# Inverter16Smd.net
KiCad netlist of a schematic drawn in EAGLE
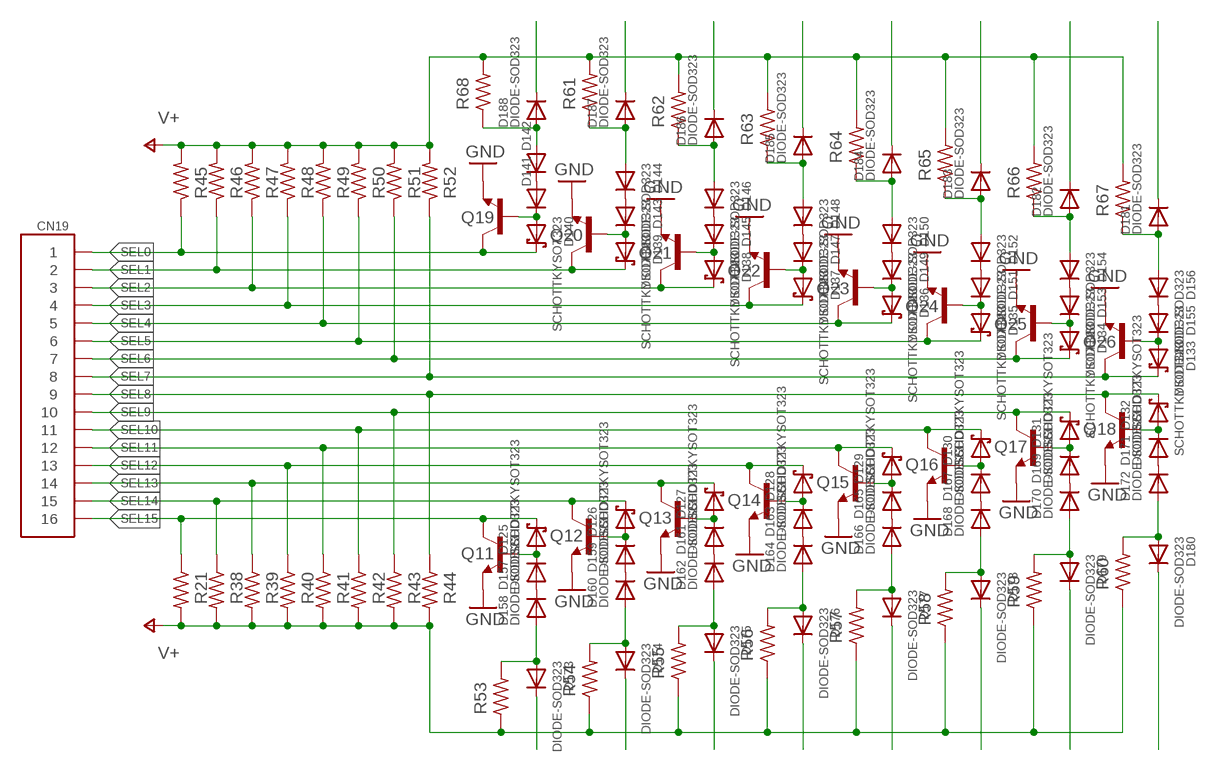
[diagram p0: schematic, sheet 1]

(export (version "E")
  (design (tool "Eeschema 10.0.6"))
  (components
    (comp (ref "CN19")
      (value "HD16")
      (footprint "eagle-import:HD16")
      (libsource (lib "eagle-import") (part "HD16"))
    )
    (comp (ref "D125")
      (value "SCHOTTKYSOT323")
      (footprint "eagle-import:SOT23")
      (libsource (lib "eagle-import") (part "SCHOTTKYSOT323"))
    )
    (comp (ref "D126")
      (value "SCHOTTKYSOT323")
      (footprint "eagle-import:SOT23")
      (libsource (lib "eagle-import") (part "SCHOTTKYSOT323"))
    )
    (comp (ref "D127")
      (value "SCHOTTKYSOT323")
      (footprint "eagle-import:SOT23")
      (libsource (lib "eagle-import") (part "SCHOTTKYSOT323"))
    )
    (comp (ref "D128")
      (value "SCHOTTKYSOT323")
      (footprint "eagle-import:SOT23")
      (libsource (lib "eagle-import") (part "SCHOTTKYSOT323"))
    )
    (comp (ref "D129")
      (value "SCHOTTKYSOT323")
      (footprint "eagle-import:SOT23")
      (libsource (lib "eagle-import") (part "SCHOTTKYSOT323"))
    )
    (comp (ref "D130")
      (value "SCHOTTKYSOT323")
      (footprint "eagle-import:SOT23")
      (libsource (lib "eagle-import") (part "SCHOTTKYSOT323"))
    )
    (comp (ref "D131")
      (value "SCHOTTKYSOT323")
      (footprint "eagle-import:SOT23")
      (libsource (lib "eagle-import") (part "SCHOTTKYSOT323"))
    )
    (comp (ref "D132")
      (value "SCHOTTKYSOT323")
      (footprint "eagle-import:SOT23")
      (libsource (lib "eagle-import") (part "SCHOTTKYSOT323"))
    )
    (comp (ref "D133")
      (value "SCHOTTKYSOT323")
      (footprint "eagle-import:SOT23")
      (libsource (lib "eagle-import") (part "SCHOTTKYSOT323"))
    )
    (comp (ref "D134")
      (value "SCHOTTKYSOT323")
      (footprint "eagle-import:SOT23")
      (libsource (lib "eagle-import") (part "SCHOTTKYSOT323"))
    )
    (comp (ref "D135")
      (value "SCHOTTKYSOT323")
      (footprint "eagle-import:SOT23")
      (libsource (lib "eagle-import") (part "SCHOTTKYSOT323"))
    )
    (comp (ref "D136")
      (value "SCHOTTKYSOT323")
      (footprint "eagle-import:SOT23")
      (libsource (lib "eagle-import") (part "SCHOTTKYSOT323"))
    )
    (comp (ref "D137")
      (value "SCHOTTKYSOT323")
      (footprint "eagle-import:SOT23")
      (libsource (lib "eagle-import") (part "SCHOTTKYSOT323"))
    )
    (comp (ref "D138")
      (value "SCHOTTKYSOT323")
      (footprint "eagle-import:SOT23")
      (libsource (lib "eagle-import") (part "SCHOTTKYSOT323"))
    )
    (comp (ref "D139")
      (value "SCHOTTKYSOT323")
      (footprint "eagle-import:SOT23")
      (libsource (lib "eagle-import") (part "SCHOTTKYSOT323"))
    )
    (comp (ref "D140")
      (value "SCHOTTKYSOT323")
      (footprint "eagle-import:SOT23")
      (libsource (lib "eagle-import") (part "SCHOTTKYSOT323"))
    )
    (comp (ref "D141")
      (value "DIODE-SOD323")
      (footprint "eagle-import:SOD323F")
      (libsource (lib "eagle-import") (part "DIODE-SOD323"))
    )
    (comp (ref "D142")
      (value "DIODE-SOD323")
      (footprint "eagle-import:SOD323F")
      (libsource (lib "eagle-import") (part "DIODE-SOD323"))
    )
    (comp (ref "D143")
      (value "DIODE-SOD323")
      (footprint "eagle-import:SOD323F")
      (libsource (lib "eagle-import") (part "DIODE-SOD323"))
    )
    (comp (ref "D144")
      (value "DIODE-SOD323")
      (footprint "eagle-import:SOD323F")
      (libsource (lib "eagle-import") (part "DIODE-SOD323"))
    )
    (comp (ref "D145")
      (value "DIODE-SOD323")
      (footprint "eagle-import:SOD323F")
      (libsource (lib "eagle-import") (part "DIODE-SOD323"))
    )
    (comp (ref "D146")
      (value "DIODE-SOD323")
      (footprint "eagle-import:SOD323F")
      (libsource (lib "eagle-import") (part "DIODE-SOD323"))
    )
    (comp (ref "D147")
      (value "DIODE-SOD323")
      (footprint "eagle-import:SOD323F")
      (libsource (lib "eagle-import") (part "DIODE-SOD323"))
    )
    (comp (ref "D148")
      (value "DIODE-SOD323")
      (footprint "eagle-import:SOD323F")
      (libsource (lib "eagle-import") (part "DIODE-SOD323"))
    )
    (comp (ref "D149")
      (value "DIODE-SOD323")
      (footprint "eagle-import:SOD323F")
      (libsource (lib "eagle-import") (part "DIODE-SOD323"))
    )
    (comp (ref "D150")
      (value "DIODE-SOD323")
      (footprint "eagle-import:SOD323F")
      (libsource (lib "eagle-import") (part "DIODE-SOD323"))
    )
    (comp (ref "D151")
      (value "DIODE-SOD323")
      (footprint "eagle-import:SOD323F")
      (libsource (lib "eagle-import") (part "DIODE-SOD323"))
    )
    (comp (ref "D152")
      (value "DIODE-SOD323")
      (footprint "eagle-import:SOD323F")
      (libsource (lib "eagle-import") (part "DIODE-SOD323"))
    )
    (comp (ref "D153")
      (value "DIODE-SOD323")
      (footprint "eagle-import:SOD323F")
      (libsource (lib "eagle-import") (part "DIODE-SOD323"))
    )
    (comp (ref "D154")
      (value "DIODE-SOD323")
      (footprint "eagle-import:SOD323F")
      (libsource (lib "eagle-import") (part "DIODE-SOD323"))
    )
    (comp (ref "D155")
      (value "DIODE-SOD323")
      (footprint "eagle-import:SOD323F")
      (libsource (lib "eagle-import") (part "DIODE-SOD323"))
    )
    (comp (ref "D156")
      (value "DIODE-SOD323")
      (footprint "eagle-import:SOD323F")
      (libsource (lib "eagle-import") (part "DIODE-SOD323"))
    )
    (comp (ref "D157")
      (value "DIODE-SOD323")
      (footprint "eagle-import:SOD323F")
      (libsource (lib "eagle-import") (part "DIODE-SOD323"))
    )
    (comp (ref "D158")
      (value "DIODE-SOD323")
      (footprint "eagle-import:SOD323F")
      (libsource (lib "eagle-import") (part "DIODE-SOD323"))
    )
    (comp (ref "D159")
      (value "DIODE-SOD323")
      (footprint "eagle-import:SOD323F")
      (libsource (lib "eagle-import") (part "DIODE-SOD323"))
    )
    (comp (ref "D160")
      (value "DIODE-SOD323")
      (footprint "eagle-import:SOD323F")
      (libsource (lib "eagle-import") (part "DIODE-SOD323"))
    )
    (comp (ref "D161")
      (value "DIODE-SOD323")
      (footprint "eagle-import:SOD323F")
      (libsource (lib "eagle-import") (part "DIODE-SOD323"))
    )
    (comp (ref "D162")
      (value "DIODE-SOD323")
      (footprint "eagle-import:SOD323F")
      (libsource (lib "eagle-import") (part "DIODE-SOD323"))
    )
    (comp (ref "D163")
      (value "DIODE-SOD323")
      (footprint "eagle-import:SOD323F")
      (libsource (lib "eagle-import") (part "DIODE-SOD323"))
    )
    (comp (ref "D164")
      (value "DIODE-SOD323")
      (footprint "eagle-import:SOD323F")
      (libsource (lib "eagle-import") (part "DIODE-SOD323"))
    )
    (comp (ref "D165")
      (value "DIODE-SOD323")
      (footprint "eagle-import:SOD323F")
      (libsource (lib "eagle-import") (part "DIODE-SOD323"))
    )
    (comp (ref "D166")
      (value "DIODE-SOD323")
      (footprint "eagle-import:SOD323F")
      (libsource (lib "eagle-import") (part "DIODE-SOD323"))
    )
    (comp (ref "D167")
      (value "DIODE-SOD323")
      (footprint "eagle-import:SOD323F")
      (libsource (lib "eagle-import") (part "DIODE-SOD323"))
    )
    (comp (ref "D168")
      (value "DIODE-SOD323")
      (footprint "eagle-import:SOD323F")
      (libsource (lib "eagle-import") (part "DIODE-SOD323"))
    )
    (comp (ref "D169")
      (value "DIODE-SOD323")
      (footprint "eagle-import:SOD323F")
      (libsource (lib "eagle-import") (part "DIODE-SOD323"))
    )
    (comp (ref "D170")
      (value "DIODE-SOD323")
      (footprint "eagle-import:SOD323F")
      (libsource (lib "eagle-import") (part "DIODE-SOD323"))
    )
    (comp (ref "D171")
      (value "DIODE-SOD323")
      (footprint "eagle-import:SOD323F")
      (libsource (lib "eagle-import") (part "DIODE-SOD323"))
    )
    (comp (ref "D172")
      (value "DIODE-SOD323")
      (footprint "eagle-import:SOD323F")
      (libsource (lib "eagle-import") (part "DIODE-SOD323"))
    )
    (comp (ref "D173")
      (value "DIODE-SOD323")
      (footprint "eagle-import:SOD323F")
      (libsource (lib "eagle-import") (part "DIODE-SOD323"))
    )
    (comp (ref "D174")
      (value "DIODE-SOD323")
      (footprint "eagle-import:SOD323F")
      (libsource (lib "eagle-import") (part "DIODE-SOD323"))
    )
    (comp (ref "D175")
      (value "DIODE-SOD323")
      (footprint "eagle-import:SOD323F")
      (libsource (lib "eagle-import") (part "DIODE-SOD323"))
    )
    (comp (ref "D176")
      (value "DIODE-SOD323")
      (footprint "eagle-import:SOD323F")
      (libsource (lib "eagle-import") (part "DIODE-SOD323"))
    )
    (comp (ref "D177")
      (value "DIODE-SOD323")
      (footprint "eagle-import:SOD323F")
      (libsource (lib "eagle-import") (part "DIODE-SOD323"))
    )
    (comp (ref "D178")
      (value "DIODE-SOD323")
      (footprint "eagle-import:SOD323F")
      (libsource (lib "eagle-import") (part "DIODE-SOD323"))
    )
    (comp (ref "D179")
      (value "DIODE-SOD323")
      (footprint "eagle-import:SOD323F")
      (libsource (lib "eagle-import") (part "DIODE-SOD323"))
    )
    (comp (ref "D180")
      (value "DIODE-SOD323")
      (footprint "eagle-import:SOD323F")
      (libsource (lib "eagle-import") (part "DIODE-SOD323"))
    )
    (comp (ref "D181")
      (value "DIODE-SOD323")
      (footprint "eagle-import:SOD323F")
      (libsource (lib "eagle-import") (part "DIODE-SOD323"))
    )
    (comp (ref "D182")
      (value "DIODE-SOD323")
      (footprint "eagle-import:SOD323F")
      (libsource (lib "eagle-import") (part "DIODE-SOD323"))
    )
    (comp (ref "D183")
      (value "DIODE-SOD323")
      (footprint "eagle-import:SOD323F")
      (libsource (lib "eagle-import") (part "DIODE-SOD323"))
    )
    (comp (ref "D184")
      (value "DIODE-SOD323")
      (footprint "eagle-import:SOD323F")
      (libsource (lib "eagle-import") (part "DIODE-SOD323"))
    )
    (comp (ref "D185")
      (value "DIODE-SOD323")
      (footprint "eagle-import:SOD323F")
      (libsource (lib "eagle-import") (part "DIODE-SOD323"))
    )
    (comp (ref "D186")
      (value "DIODE-SOD323")
      (footprint "eagle-import:SOD323F")
      (libsource (lib "eagle-import") (part "DIODE-SOD323"))
    )
    (comp (ref "D187")
      (value "DIODE-SOD323")
      (footprint "eagle-import:SOD323F")
      (libsource (lib "eagle-import") (part "DIODE-SOD323"))
    )
    (comp (ref "D188")
      (value "DIODE-SOD323")
      (footprint "eagle-import:SOD323F")
      (libsource (lib "eagle-import") (part "DIODE-SOD323"))
    )
    (comp (ref "Q11")
      (value "BC547-SOT23")
      (footprint "eagle-import:SOT23")
      (libsource (lib "eagle-import") (part "BC547-SOT23"))
    )
    (comp (ref "Q12")
      (value "BC547-SOT23")
      (footprint "eagle-import:SOT23")
      (libsource (lib "eagle-import") (part "BC547-SOT23"))
    )
    (comp (ref "Q13")
      (value "BC547-SOT23")
      (footprint "eagle-import:SOT23")
      (libsource (lib "eagle-import") (part "BC547-SOT23"))
    )
    (comp (ref "Q14")
      (value "BC547-SOT23")
      (footprint "eagle-import:SOT23")
      (libsource (lib "eagle-import") (part "BC547-SOT23"))
    )
    (comp (ref "Q15")
      (value "BC547-SOT23")
      (footprint "eagle-import:SOT23")
      (libsource (lib "eagle-import") (part "BC547-SOT23"))
    )
    (comp (ref "Q16")
      (value "BC547-SOT23")
      (footprint "eagle-import:SOT23")
      (libsource (lib "eagle-import") (part "BC547-SOT23"))
    )
    (comp (ref "Q17")
      (value "BC547-SOT23")
      (footprint "eagle-import:SOT23")
      (libsource (lib "eagle-import") (part "BC547-SOT23"))
    )
    (comp (ref "Q18")
      (value "BC547-SOT23")
      (footprint "eagle-import:SOT23")
      (libsource (lib "eagle-import") (part "BC547-SOT23"))
    )
    (comp (ref "Q19")
      (value "BC547-SOT23")
      (footprint "eagle-import:SOT23")
      (libsource (lib "eagle-import") (part "BC547-SOT23"))
    )
    (comp (ref "Q20")
      (value "BC547-SOT23")
      (footprint "eagle-import:SOT23")
      (libsource (lib "eagle-import") (part "BC547-SOT23"))
    )
    (comp (ref "Q21")
      (value "BC547-SOT23")
      (footprint "eagle-import:SOT23")
      (libsource (lib "eagle-import") (part "BC547-SOT23"))
    )
    (comp (ref "Q22")
      (value "BC547-SOT23")
      (footprint "eagle-import:SOT23")
      (libsource (lib "eagle-import") (part "BC547-SOT23"))
    )
    (comp (ref "Q23")
      (value "BC547-SOT23")
      (footprint "eagle-import:SOT23")
      (libsource (lib "eagle-import") (part "BC547-SOT23"))
    )
    (comp (ref "Q24")
      (value "BC547-SOT23")
      (footprint "eagle-import:SOT23")
      (libsource (lib "eagle-import") (part "BC547-SOT23"))
    )
    (comp (ref "Q25")
      (value "BC547-SOT23")
      (footprint "eagle-import:SOT23")
      (libsource (lib "eagle-import") (part "BC547-SOT23"))
    )
    (comp (ref "Q26")
      (value "BC547-SOT23")
      (footprint "eagle-import:SOT23")
      (libsource (lib "eagle-import") (part "BC547-SOT23"))
    )
    (comp (ref "R21")
      (value "R-0805")
      (footprint "eagle-import:R0805")
      (libsource (lib "eagle-import") (part "R-0805"))
    )
    (comp (ref "R38")
      (value "R-0805")
      (footprint "eagle-import:R0805")
      (libsource (lib "eagle-import") (part "R-0805"))
    )
    (comp (ref "R39")
      (value "R-0805")
      (footprint "eagle-import:R0805")
      (libsource (lib "eagle-import") (part "R-0805"))
    )
    (comp (ref "R40")
      (value "R-0805")
      (footprint "eagle-import:R0805")
      (libsource (lib "eagle-import") (part "R-0805"))
    )
    (comp (ref "R41")
      (value "R-0805")
      (footprint "eagle-import:R0805")
      (libsource (lib "eagle-import") (part "R-0805"))
    )
    (comp (ref "R42")
      (value "R-0805")
      (footprint "eagle-import:R0805")
      (libsource (lib "eagle-import") (part "R-0805"))
    )
    (comp (ref "R43")
      (value "R-0805")
      (footprint "eagle-import:R0805")
      (libsource (lib "eagle-import") (part "R-0805"))
    )
    (comp (ref "R44")
      (value "R-0805")
      (footprint "eagle-import:R0805")
      (libsource (lib "eagle-import") (part "R-0805"))
    )
    (comp (ref "R45")
      (value "R-0805")
      (footprint "eagle-import:R0805")
      (libsource (lib "eagle-import") (part "R-0805"))
    )
    (comp (ref "R46")
      (value "R-0805")
      (footprint "eagle-import:R0805")
      (libsource (lib "eagle-import") (part "R-0805"))
    )
    (comp (ref "R47")
      (value "R-0805")
      (footprint "eagle-import:R0805")
      (libsource (lib "eagle-import") (part "R-0805"))
    )
    (comp (ref "R48")
      (value "R-0805")
      (footprint "eagle-import:R0805")
      (libsource (lib "eagle-import") (part "R-0805"))
    )
    (comp (ref "R49")
      (value "R-0805")
      (footprint "eagle-import:R0805")
      (libsource (lib "eagle-import") (part "R-0805"))
    )
    (comp (ref "R50")
      (value "R-0805")
      (footprint "eagle-import:R0805")
      (libsource (lib "eagle-import") (part "R-0805"))
    )
    (comp (ref "R51")
      (value "R-0805")
      (footprint "eagle-import:R0805")
      (libsource (lib "eagle-import") (part "R-0805"))
    )
    (comp (ref "R52")
      (value "R-0805")
      (footprint "eagle-import:R0805")
      (libsource (lib "eagle-import") (part "R-0805"))
    )
    (comp (ref "R53")
      (value "R-0805")
      (footprint "eagle-import:R0805")
      (libsource (lib "eagle-import") (part "R-0805"))
    )
    (comp (ref "R54")
      (value "R-0805")
      (footprint "eagle-import:R0805")
      (libsource (lib "eagle-import") (part "R-0805"))
    )
    (comp (ref "R55")
      (value "R-0805")
      (footprint "eagle-import:R0805")
      (libsource (lib "eagle-import") (part "R-0805"))
    )
    (comp (ref "R56")
      (value "R-0805")
      (footprint "eagle-import:R0805")
      (libsource (lib "eagle-import") (part "R-0805"))
    )
    (comp (ref "R57")
      (value "R-0805")
      (footprint "eagle-import:R0805")
      (libsource (lib "eagle-import") (part "R-0805"))
    )
    (comp (ref "R58")
      (value "R-0805")
      (footprint "eagle-import:R0805")
      (libsource (lib "eagle-import") (part "R-0805"))
    )
    (comp (ref "R59")
      (value "R-0805")
      (footprint "eagle-import:R0805")
      (libsource (lib "eagle-import") (part "R-0805"))
    )
    (comp (ref "R60")
      (value "R-0805")
      (footprint "eagle-import:R0805")
      (libsource (lib "eagle-import") (part "R-0805"))
    )
    (comp (ref "R61")
      (value "R-0805")
      (footprint "eagle-import:R0805")
      (libsource (lib "eagle-import") (part "R-0805"))
    )
    (comp (ref "R62")
      (value "R-0805")
      (footprint "eagle-import:R0805")
      (libsource (lib "eagle-import") (part "R-0805"))
    )
    (comp (ref "R63")
      (value "R-0805")
      (footprint "eagle-import:R0805")
      (libsource (lib "eagle-import") (part "R-0805"))
    )
    (comp (ref "R64")
      (value "R-0805")
      (footprint "eagle-import:R0805")
      (libsource (lib "eagle-import") (part "R-0805"))
    )
    (comp (ref "R65")
      (value "R-0805")
      (footprint "eagle-import:R0805")
      (libsource (lib "eagle-import") (part "R-0805"))
    )
    (comp (ref "R66")
      (value "R-0805")
      (footprint "eagle-import:R0805")
      (libsource (lib "eagle-import") (part "R-0805"))
    )
    (comp (ref "R67")
      (value "R-0805")
      (footprint "eagle-import:R0805")
      (libsource (lib "eagle-import") (part "R-0805"))
    )
    (comp (ref "R68")
      (value "R-0805")
      (footprint "eagle-import:R0805")
      (libsource (lib "eagle-import") (part "R-0805"))
    )
  )
  (nets
    (net (code "1") (name "GND") (class "Default")
      (node (ref "Q11") (pin "2") (pinfunction "E_2") (pintype "passive"))
      (node (ref "Q12") (pin "2") (pinfunction "E_2") (pintype "passive"))
      (node (ref "Q13") (pin "2") (pinfunction "E_2") (pintype "passive"))
      (node (ref "Q14") (pin "2") (pinfunction "E_2") (pintype "passive"))
      (node (ref "Q15") (pin "2") (pinfunction "E_2") (pintype "passive"))
      (node (ref "Q16") (pin "2") (pinfunction "E_2") (pintype "passive"))
      (node (ref "Q17") (pin "2") (pinfunction "E_2") (pintype "passive"))
      (node (ref "Q18") (pin "2") (pinfunction "E_2") (pintype "passive"))
      (node (ref "Q19") (pin "2") (pinfunction "E_2") (pintype "passive"))
      (node (ref "Q20") (pin "2") (pinfunction "E_2") (pintype "passive"))
      (node (ref "Q21") (pin "2") (pinfunction "E_2") (pintype "passive"))
      (node (ref "Q22") (pin "2") (pinfunction "E_2") (pintype "passive"))
      (node (ref "Q23") (pin "2") (pinfunction "E_2") (pintype "passive"))
      (node (ref "Q24") (pin "2") (pinfunction "E_2") (pintype "passive"))
      (node (ref "Q25") (pin "2") (pinfunction "E_2") (pintype "passive"))
      (node (ref "Q26") (pin "2") (pinfunction "E_2") (pintype "passive"))
    )
    (net (code "2") (name "Net-(D125-A)") (class "Default")
      (node (ref "D125") (pin "1") (pinfunction "A_1") (pintype "passive"))
      (node (ref "D157") (pin "C") (pinfunction "C_C") (pintype "passive"))
      (node (ref "Q11") (pin "1") (pinfunction "B_1") (pintype "passive"))
    )
    (net (code "3") (name "Net-(D126-A)") (class "Default")
      (node (ref "D126") (pin "1") (pinfunction "A_1") (pintype "passive"))
      (node (ref "D159") (pin "C") (pinfunction "C_C") (pintype "passive"))
      (node (ref "Q12") (pin "1") (pinfunction "B_1") (pintype "passive"))
    )
    (net (code "4") (name "Net-(D127-A)") (class "Default")
      (node (ref "D127") (pin "1") (pinfunction "A_1") (pintype "passive"))
      (node (ref "D161") (pin "C") (pinfunction "C_C") (pintype "passive"))
      (node (ref "Q13") (pin "1") (pinfunction "B_1") (pintype "passive"))
    )
    (net (code "5") (name "Net-(D128-A)") (class "Default")
      (node (ref "D128") (pin "1") (pinfunction "A_1") (pintype "passive"))
      (node (ref "D163") (pin "C") (pinfunction "C_C") (pintype "passive"))
      (node (ref "Q14") (pin "1") (pinfunction "B_1") (pintype "passive"))
    )
    (net (code "6") (name "Net-(D129-A)") (class "Default")
      (node (ref "D129") (pin "1") (pinfunction "A_1") (pintype "passive"))
      (node (ref "D165") (pin "C") (pinfunction "C_C") (pintype "passive"))
      (node (ref "Q15") (pin "1") (pinfunction "B_1") (pintype "passive"))
    )
    (net (code "7") (name "Net-(D130-A)") (class "Default")
      (node (ref "D130") (pin "1") (pinfunction "A_1") (pintype "passive"))
      (node (ref "D167") (pin "C") (pinfunction "C_C") (pintype "passive"))
      (node (ref "Q16") (pin "1") (pinfunction "B_1") (pintype "passive"))
    )
    (net (code "8") (name "Net-(D131-A)") (class "Default")
      (node (ref "D131") (pin "1") (pinfunction "A_1") (pintype "passive"))
      (node (ref "D169") (pin "C") (pinfunction "C_C") (pintype "passive"))
      (node (ref "Q17") (pin "1") (pinfunction "B_1") (pintype "passive"))
    )
    (net (code "9") (name "Net-(D132-A)") (class "Default")
      (node (ref "D132") (pin "1") (pinfunction "A_1") (pintype "passive"))
      (node (ref "D171") (pin "C") (pinfunction "C_C") (pintype "passive"))
      (node (ref "Q18") (pin "1") (pinfunction "B_1") (pintype "passive"))
    )
    (net (code "10") (name "Net-(D133-A)") (class "Default")
      (node (ref "D133") (pin "1") (pinfunction "A_1") (pintype "passive"))
      (node (ref "D155") (pin "C") (pinfunction "C_C") (pintype "passive"))
      (node (ref "Q26") (pin "1") (pinfunction "B_1") (pintype "passive"))
    )
    (net (code "11") (name "Net-(D134-A)") (class "Default")
      (node (ref "D134") (pin "1") (pinfunction "A_1") (pintype "passive"))
      (node (ref "D153") (pin "C") (pinfunction "C_C") (pintype "passive"))
      (node (ref "Q25") (pin "1") (pinfunction "B_1") (pintype "passive"))
    )
    (net (code "12") (name "Net-(D135-A)") (class "Default")
      (node (ref "D135") (pin "1") (pinfunction "A_1") (pintype "passive"))
      (node (ref "D151") (pin "C") (pinfunction "C_C") (pintype "passive"))
      (node (ref "Q24") (pin "1") (pinfunction "B_1") (pintype "passive"))
    )
    (net (code "13") (name "Net-(D136-A)") (class "Default")
      (node (ref "D136") (pin "1") (pinfunction "A_1") (pintype "passive"))
      (node (ref "D149") (pin "C") (pinfunction "C_C") (pintype "passive"))
      (node (ref "Q23") (pin "1") (pinfunction "B_1") (pintype "passive"))
    )
    (net (code "14") (name "Net-(D137-A)") (class "Default")
      (node (ref "D137") (pin "1") (pinfunction "A_1") (pintype "passive"))
      (node (ref "D147") (pin "C") (pinfunction "C_C") (pintype "passive"))
      (node (ref "Q22") (pin "1") (pinfunction "B_1") (pintype "passive"))
    )
    (net (code "15") (name "Net-(D138-A)") (class "Default")
      (node (ref "D138") (pin "1") (pinfunction "A_1") (pintype "passive"))
      (node (ref "D145") (pin "C") (pinfunction "C_C") (pintype "passive"))
      (node (ref "Q21") (pin "1") (pinfunction "B_1") (pintype "passive"))
    )
    (net (code "16") (name "Net-(D139-A)") (class "Default")
      (node (ref "D139") (pin "1") (pinfunction "A_1") (pintype "passive"))
      (node (ref "D143") (pin "C") (pinfunction "C_C") (pintype "passive"))
      (node (ref "Q20") (pin "1") (pinfunction "B_1") (pintype "passive"))
    )
    (net (code "17") (name "Net-(D140-A)") (class "Default")
      (node (ref "D140") (pin "1") (pinfunction "A_1") (pintype "passive"))
      (node (ref "D141") (pin "C") (pinfunction "C_C") (pintype "passive"))
      (node (ref "Q19") (pin "1") (pinfunction "B_1") (pintype "passive"))
    )
    (net (code "18") (name "Net-(D141-PadA)") (class "Default")
      (node (ref "D141") (pin "A") (pinfunction "A_A") (pintype "passive"))
      (node (ref "D142") (pin "C") (pinfunction "C_C") (pintype "passive"))
    )
    (net (code "19") (name "Net-(D142-PadA)") (class "Default")
      (node (ref "D142") (pin "A") (pinfunction "A_A") (pintype "passive"))
      (node (ref "D188") (pin "A") (pinfunction "A_A") (pintype "passive"))
      (node (ref "R68") (pin "1") (pinfunction "1_1") (pintype "passive"))
    )
    (net (code "20") (name "Net-(D143-PadA)") (class "Default")
      (node (ref "D143") (pin "A") (pinfunction "A_A") (pintype "passive"))
      (node (ref "D144") (pin "C") (pinfunction "C_C") (pintype "passive"))
    )
    (net (code "21") (name "Net-(D144-PadA)") (class "Default")
      (node (ref "D144") (pin "A") (pinfunction "A_A") (pintype "passive"))
      (node (ref "D187") (pin "A") (pinfunction "A_A") (pintype "passive"))
      (node (ref "R61") (pin "1") (pinfunction "1_1") (pintype "passive"))
    )
    (net (code "22") (name "Net-(D145-PadA)") (class "Default")
      (node (ref "D145") (pin "A") (pinfunction "A_A") (pintype "passive"))
      (node (ref "D146") (pin "C") (pinfunction "C_C") (pintype "passive"))
    )
    (net (code "23") (name "Net-(D146-PadA)") (class "Default")
      (node (ref "D146") (pin "A") (pinfunction "A_A") (pintype "passive"))
      (node (ref "D186") (pin "A") (pinfunction "A_A") (pintype "passive"))
      (node (ref "R62") (pin "1") (pinfunction "1_1") (pintype "passive"))
    )
    (net (code "24") (name "Net-(D147-PadA)") (class "Default")
      (node (ref "D147") (pin "A") (pinfunction "A_A") (pintype "passive"))
      (node (ref "D148") (pin "C") (pinfunction "C_C") (pintype "passive"))
    )
    (net (code "25") (name "Net-(D148-PadA)") (class "Default")
      (node (ref "D148") (pin "A") (pinfunction "A_A") (pintype "passive"))
      (node (ref "D185") (pin "A") (pinfunction "A_A") (pintype "passive"))
      (node (ref "R63") (pin "1") (pinfunction "1_1") (pintype "passive"))
    )
    (net (code "26") (name "Net-(D149-PadA)") (class "Default")
      (node (ref "D149") (pin "A") (pinfunction "A_A") (pintype "passive"))
      (node (ref "D150") (pin "C") (pinfunction "C_C") (pintype "passive"))
    )
    (net (code "27") (name "Net-(D150-PadA)") (class "Default")
      (node (ref "D150") (pin "A") (pinfunction "A_A") (pintype "passive"))
      (node (ref "D184") (pin "A") (pinfunction "A_A") (pintype "passive"))
      (node (ref "R64") (pin "1") (pinfunction "1_1") (pintype "passive"))
    )
    (net (code "28") (name "Net-(D151-PadA)") (class "Default")
      (node (ref "D151") (pin "A") (pinfunction "A_A") (pintype "passive"))
      (node (ref "D152") (pin "C") (pinfunction "C_C") (pintype "passive"))
    )
    (net (code "29") (name "Net-(D152-PadA)") (class "Default")
      (node (ref "D152") (pin "A") (pinfunction "A_A") (pintype "passive"))
      (node (ref "D183") (pin "A") (pinfunction "A_A") (pintype "passive"))
      (node (ref "R65") (pin "1") (pinfunction "1_1") (pintype "passive"))
    )
    (net (code "30") (name "Net-(D153-PadA)") (class "Default")
      (node (ref "D153") (pin "A") (pinfunction "A_A") (pintype "passive"))
      (node (ref "D154") (pin "C") (pinfunction "C_C") (pintype "passive"))
    )
    (net (code "31") (name "Net-(D154-PadA)") (class "Default")
      (node (ref "D154") (pin "A") (pinfunction "A_A") (pintype "passive"))
      (node (ref "D182") (pin "A") (pinfunction "A_A") (pintype "passive"))
      (node (ref "R66") (pin "1") (pinfunction "1_1") (pintype "passive"))
    )
    (net (code "32") (name "Net-(D155-PadA)") (class "Default")
      (node (ref "D155") (pin "A") (pinfunction "A_A") (pintype "passive"))
      (node (ref "D156") (pin "C") (pinfunction "C_C") (pintype "passive"))
    )
    (net (code "33") (name "Net-(D156-PadA)") (class "Default")
      (node (ref "D156") (pin "A") (pinfunction "A_A") (pintype "passive"))
      (node (ref "D181") (pin "A") (pinfunction "A_A") (pintype "passive"))
      (node (ref "R67") (pin "1") (pinfunction "1_1") (pintype "passive"))
    )
    (net (code "34") (name "Net-(D157-PadA)") (class "Default")
      (node (ref "D157") (pin "A") (pinfunction "A_A") (pintype "passive"))
      (node (ref "D158") (pin "C") (pinfunction "C_C") (pintype "passive"))
    )
    (net (code "35") (name "Net-(D158-PadA)") (class "Default")
      (node (ref "D158") (pin "A") (pinfunction "A_A") (pintype "passive"))
      (node (ref "D173") (pin "A") (pinfunction "A_A") (pintype "passive"))
      (node (ref "R53") (pin "2") (pinfunction "2_2") (pintype "passive"))
    )
    (net (code "36") (name "Net-(D159-PadA)") (class "Default")
      (node (ref "D159") (pin "A") (pinfunction "A_A") (pintype "passive"))
      (node (ref "D160") (pin "C") (pinfunction "C_C") (pintype "passive"))
    )
    (net (code "37") (name "Net-(D160-PadA)") (class "Default")
      (node (ref "D160") (pin "A") (pinfunction "A_A") (pintype "passive"))
      (node (ref "D174") (pin "A") (pinfunction "A_A") (pintype "passive"))
      (node (ref "R54") (pin "2") (pinfunction "2_2") (pintype "passive"))
    )
    (net (code "38") (name "Net-(D161-PadA)") (class "Default")
      (node (ref "D161") (pin "A") (pinfunction "A_A") (pintype "passive"))
      (node (ref "D162") (pin "C") (pinfunction "C_C") (pintype "passive"))
    )
    (net (code "39") (name "Net-(D162-PadA)") (class "Default")
      (node (ref "D162") (pin "A") (pinfunction "A_A") (pintype "passive"))
      (node (ref "D175") (pin "A") (pinfunction "A_A") (pintype "passive"))
      (node (ref "R55") (pin "2") (pinfunction "2_2") (pintype "passive"))
    )
    (net (code "40") (name "Net-(D163-PadA)") (class "Default")
      (node (ref "D163") (pin "A") (pinfunction "A_A") (pintype "passive"))
      (node (ref "D164") (pin "C") (pinfunction "C_C") (pintype "passive"))
    )
    (net (code "41") (name "Net-(D164-PadA)") (class "Default")
      (node (ref "D164") (pin "A") (pinfunction "A_A") (pintype "passive"))
      (node (ref "D176") (pin "A") (pinfunction "A_A") (pintype "passive"))
      (node (ref "R56") (pin "2") (pinfunction "2_2") (pintype "passive"))
    )
    (net (code "42") (name "Net-(D165-PadA)") (class "Default")
      (node (ref "D165") (pin "A") (pinfunction "A_A") (pintype "passive"))
      (node (ref "D166") (pin "C") (pinfunction "C_C") (pintype "passive"))
    )
    (net (code "43") (name "Net-(D166-PadA)") (class "Default")
      (node (ref "D166") (pin "A") (pinfunction "A_A") (pintype "passive"))
      (node (ref "D177") (pin "A") (pinfunction "A_A") (pintype "passive"))
      (node (ref "R57") (pin "2") (pinfunction "2_2") (pintype "passive"))
    )
    (net (code "44") (name "Net-(D167-PadA)") (class "Default")
      (node (ref "D167") (pin "A") (pinfunction "A_A") (pintype "passive"))
      (node (ref "D168") (pin "C") (pinfunction "C_C") (pintype "passive"))
    )
    (net (code "45") (name "Net-(D168-PadA)") (class "Default")
      (node (ref "D168") (pin "A") (pinfunction "A_A") (pintype "passive"))
      (node (ref "D178") (pin "A") (pinfunction "A_A") (pintype "passive"))
      (node (ref "R58") (pin "2") (pinfunction "2_2") (pintype "passive"))
    )
    (net (code "46") (name "Net-(D169-PadA)") (class "Default")
      (node (ref "D169") (pin "A") (pinfunction "A_A") (pintype "passive"))
      (node (ref "D170") (pin "C") (pinfunction "C_C") (pintype "passive"))
    )
    (net (code "47") (name "Net-(D170-PadA)") (class "Default")
      (node (ref "D170") (pin "A") (pinfunction "A_A") (pintype "passive"))
      (node (ref "D179") (pin "A") (pinfunction "A_A") (pintype "passive"))
      (node (ref "R59") (pin "2") (pinfunction "2_2") (pintype "passive"))
    )
    (net (code "48") (name "Net-(D171-PadA)") (class "Default")
      (node (ref "D171") (pin "A") (pinfunction "A_A") (pintype "passive"))
      (node (ref "D172") (pin "C") (pinfunction "C_C") (pintype "passive"))
    )
    (net (code "49") (name "Net-(D172-PadA)") (class "Default")
      (node (ref "D172") (pin "A") (pinfunction "A_A") (pintype "passive"))
      (node (ref "D180") (pin "A") (pinfunction "A_A") (pintype "passive"))
      (node (ref "R60") (pin "2") (pinfunction "2_2") (pintype "passive"))
    )
    (net (code "50") (name "SEL0") (class "Default")
      (node (ref "CN19") (pin "P$1") (pinfunction "1_P$1") (pintype "bidirectional"))
      (node (ref "D140") (pin "3") (pinfunction "C_3") (pintype "passive"))
      (node (ref "Q19") (pin "3") (pinfunction "C_3") (pintype "passive"))
      (node (ref "R45") (pin "1") (pinfunction "1_1") (pintype "passive"))
    )
    (net (code "51") (name "SEL1") (class "Default")
      (node (ref "CN19") (pin "P$2") (pinfunction "2_P$2") (pintype "bidirectional"))
      (node (ref "D139") (pin "3") (pinfunction "C_3") (pintype "passive"))
      (node (ref "Q20") (pin "3") (pinfunction "C_3") (pintype "passive"))
      (node (ref "R46") (pin "1") (pinfunction "1_1") (pintype "passive"))
    )
    (net (code "52") (name "SEL2") (class "Default")
      (node (ref "CN19") (pin "P$3") (pinfunction "3_P$3") (pintype "bidirectional"))
      (node (ref "D138") (pin "3") (pinfunction "C_3") (pintype "passive"))
      (node (ref "Q21") (pin "3") (pinfunction "C_3") (pintype "passive"))
      (node (ref "R47") (pin "1") (pinfunction "1_1") (pintype "passive"))
    )
    (net (code "53") (name "SEL3") (class "Default")
      (node (ref "CN19") (pin "P$4") (pinfunction "4_P$4") (pintype "bidirectional"))
      (node (ref "D137") (pin "3") (pinfunction "C_3") (pintype "passive"))
      (node (ref "Q22") (pin "3") (pinfunction "C_3") (pintype "passive"))
      (node (ref "R48") (pin "1") (pinfunction "1_1") (pintype "passive"))
    )
    (net (code "54") (name "SEL4") (class "Default")
      (node (ref "CN19") (pin "P$5") (pinfunction "5_P$5") (pintype "bidirectional"))
      (node (ref "D136") (pin "3") (pinfunction "C_3") (pintype "passive"))
      (node (ref "Q23") (pin "3") (pinfunction "C_3") (pintype "passive"))
      (node (ref "R49") (pin "1") (pinfunction "1_1") (pintype "passive"))
    )
    (net (code "55") (name "SEL5") (class "Default")
      (node (ref "CN19") (pin "P$6") (pinfunction "6_P$6") (pintype "bidirectional"))
      (node (ref "D135") (pin "3") (pinfunction "C_3") (pintype "passive"))
      (node (ref "Q24") (pin "3") (pinfunction "C_3") (pintype "passive"))
      (node (ref "R50") (pin "1") (pinfunction "1_1") (pintype "passive"))
    )
    (net (code "56") (name "SEL6") (class "Default")
      (node (ref "CN19") (pin "P$7") (pinfunction "7_P$7") (pintype "bidirectional"))
      (node (ref "D134") (pin "3") (pinfunction "C_3") (pintype "passive"))
      (node (ref "Q25") (pin "3") (pinfunction "C_3") (pintype "passive"))
      (node (ref "R51") (pin "1") (pinfunction "1_1") (pintype "passive"))
    )
    (net (code "57") (name "SEL7") (class "Default")
      (node (ref "CN19") (pin "P$8") (pinfunction "8_P$8") (pintype "bidirectional"))
      (node (ref "D133") (pin "3") (pinfunction "C_3") (pintype "passive"))
      (node (ref "Q26") (pin "3") (pinfunction "C_3") (pintype "passive"))
      (node (ref "R52") (pin "1") (pinfunction "1_1") (pintype "passive"))
    )
    (net (code "58") (name "SEL8") (class "Default")
      (node (ref "CN19") (pin "P$9") (pinfunction "9_P$9") (pintype "bidirectional"))
      (node (ref "D132") (pin "3") (pinfunction "C_3") (pintype "passive"))
      (node (ref "Q18") (pin "3") (pinfunction "C_3") (pintype "passive"))
      (node (ref "R44") (pin "1") (pinfunction "1_1") (pintype "passive"))
    )
    (net (code "59") (name "SEL9") (class "Default")
      (node (ref "CN19") (pin "P$10") (pinfunction "10_P$10") (pintype "bidirectional"))
      (node (ref "D131") (pin "3") (pinfunction "C_3") (pintype "passive"))
      (node (ref "Q17") (pin "3") (pinfunction "C_3") (pintype "passive"))
      (node (ref "R43") (pin "1") (pinfunction "1_1") (pintype "passive"))
    )
    (net (code "60") (name "SEL10") (class "Default")
      (node (ref "CN19") (pin "P$11") (pinfunction "11_P$11") (pintype "bidirectional"))
      (node (ref "D130") (pin "3") (pinfunction "C_3") (pintype "passive"))
      (node (ref "Q16") (pin "3") (pinfunction "C_3") (pintype "passive"))
      (node (ref "R42") (pin "1") (pinfunction "1_1") (pintype "passive"))
    )
    (net (code "61") (name "SEL11") (class "Default")
      (node (ref "CN19") (pin "P$12") (pinfunction "12_P$12") (pintype "bidirectional"))
      (node (ref "D129") (pin "3") (pinfunction "C_3") (pintype "passive"))
      (node (ref "Q15") (pin "3") (pinfunction "C_3") (pintype "passive"))
      (node (ref "R41") (pin "1") (pinfunction "1_1") (pintype "passive"))
    )
    (net (code "62") (name "SEL12") (class "Default")
      (node (ref "CN19") (pin "P$13") (pinfunction "13_P$13") (pintype "bidirectional"))
      (node (ref "D128") (pin "3") (pinfunction "C_3") (pintype "passive"))
      (node (ref "Q14") (pin "3") (pinfunction "C_3") (pintype "passive"))
      (node (ref "R40") (pin "1") (pinfunction "1_1") (pintype "passive"))
    )
    (net (code "63") (name "SEL13") (class "Default")
      (node (ref "CN19") (pin "P$14") (pinfunction "14_P$14") (pintype "bidirectional"))
      (node (ref "D127") (pin "3") (pinfunction "C_3") (pintype "passive"))
      (node (ref "Q13") (pin "3") (pinfunction "C_3") (pintype "passive"))
      (node (ref "R39") (pin "1") (pinfunction "1_1") (pintype "passive"))
    )
    (net (code "64") (name "SEL14") (class "Default")
      (node (ref "CN19") (pin "P$15") (pinfunction "15_P$15") (pintype "bidirectional"))
      (node (ref "D126") (pin "3") (pinfunction "C_3") (pintype "passive"))
      (node (ref "Q12") (pin "3") (pinfunction "C_3") (pintype "passive"))
      (node (ref "R38") (pin "1") (pinfunction "1_1") (pintype "passive"))
    )
    (net (code "65") (name "SEL15") (class "Default")
      (node (ref "CN19") (pin "P$16") (pinfunction "16_P$16") (pintype "bidirectional"))
      (node (ref "D125") (pin "3") (pinfunction "C_3") (pintype "passive"))
      (node (ref "Q11") (pin "3") (pinfunction "C_3") (pintype "passive"))
      (node (ref "R21") (pin "1") (pinfunction "1_1") (pintype "passive"))
    )
    (net (code "66") (name "V+") (class "Default")
      (node (ref "R21") (pin "2") (pinfunction "2_2") (pintype "passive"))
      (node (ref "R38") (pin "2") (pinfunction "2_2") (pintype "passive"))
      (node (ref "R39") (pin "2") (pinfunction "2_2") (pintype "passive"))
      (node (ref "R40") (pin "2") (pinfunction "2_2") (pintype "passive"))
      (node (ref "R41") (pin "2") (pinfunction "2_2") (pintype "passive"))
      (node (ref "R42") (pin "2") (pinfunction "2_2") (pintype "passive"))
      (node (ref "R43") (pin "2") (pinfunction "2_2") (pintype "passive"))
      (node (ref "R44") (pin "2") (pinfunction "2_2") (pintype "passive"))
      (node (ref "R45") (pin "2") (pinfunction "2_2") (pintype "passive"))
      (node (ref "R46") (pin "2") (pinfunction "2_2") (pintype "passive"))
      (node (ref "R47") (pin "2") (pinfunction "2_2") (pintype "passive"))
      (node (ref "R48") (pin "2") (pinfunction "2_2") (pintype "passive"))
      (node (ref "R49") (pin "2") (pinfunction "2_2") (pintype "passive"))
      (node (ref "R50") (pin "2") (pinfunction "2_2") (pintype "passive"))
      (node (ref "R51") (pin "2") (pinfunction "2_2") (pintype "passive"))
      (node (ref "R52") (pin "2") (pinfunction "2_2") (pintype "passive"))
      (node (ref "R53") (pin "1") (pinfunction "1_1") (pintype "passive"))
      (node (ref "R54") (pin "1") (pinfunction "1_1") (pintype "passive"))
      (node (ref "R55") (pin "1") (pinfunction "1_1") (pintype "passive"))
      (node (ref "R56") (pin "1") (pinfunction "1_1") (pintype "passive"))
      (node (ref "R57") (pin "1") (pinfunction "1_1") (pintype "passive"))
      (node (ref "R58") (pin "1") (pinfunction "1_1") (pintype "passive"))
      (node (ref "R59") (pin "1") (pinfunction "1_1") (pintype "passive"))
      (node (ref "R60") (pin "1") (pinfunction "1_1") (pintype "passive"))
      (node (ref "R61") (pin "2") (pinfunction "2_2") (pintype "passive"))
      (node (ref "R62") (pin "2") (pinfunction "2_2") (pintype "passive"))
      (node (ref "R63") (pin "2") (pinfunction "2_2") (pintype "passive"))
      (node (ref "R64") (pin "2") (pinfunction "2_2") (pintype "passive"))
      (node (ref "R65") (pin "2") (pinfunction "2_2") (pintype "passive"))
      (node (ref "R66") (pin "2") (pinfunction "2_2") (pintype "passive"))
      (node (ref "R67") (pin "2") (pinfunction "2_2") (pintype "passive"))
      (node (ref "R68") (pin "2") (pinfunction "2_2") (pintype "passive"))
    )
    (net (code "67") (name "unconnected-(D173-PadC)") (class "Default")
      (node (ref "D173") (pin "C") (pinfunction "C_C") (pintype "passive"))
    )
    (net (code "68") (name "unconnected-(D174-PadC)") (class "Default")
      (node (ref "D174") (pin "C") (pinfunction "C_C") (pintype "passive"))
    )
    (net (code "69") (name "unconnected-(D175-PadC)") (class "Default")
      (node (ref "D175") (pin "C") (pinfunction "C_C") (pintype "passive"))
    )
    (net (code "70") (name "unconnected-(D176-PadC)") (class "Default")
      (node (ref "D176") (pin "C") (pinfunction "C_C") (pintype "passive"))
    )
    (net (code "71") (name "unconnected-(D177-PadC)") (class "Default")
      (node (ref "D177") (pin "C") (pinfunction "C_C") (pintype "passive"))
    )
    (net (code "72") (name "unconnected-(D178-PadC)") (class "Default")
      (node (ref "D178") (pin "C") (pinfunction "C_C") (pintype "passive"))
    )
    (net (code "73") (name "unconnected-(D179-PadC)") (class "Default")
      (node (ref "D179") (pin "C") (pinfunction "C_C") (pintype "passive"))
    )
    (net (code "74") (name "unconnected-(D180-PadC)") (class "Default")
      (node (ref "D180") (pin "C") (pinfunction "C_C") (pintype "passive"))
    )
    (net (code "75") (name "unconnected-(D181-PadC)") (class "Default")
      (node (ref "D181") (pin "C") (pinfunction "C_C") (pintype "passive"))
    )
    (net (code "76") (name "unconnected-(D182-PadC)") (class "Default")
      (node (ref "D182") (pin "C") (pinfunction "C_C") (pintype "passive"))
    )
    (net (code "77") (name "unconnected-(D183-PadC)") (class "Default")
      (node (ref "D183") (pin "C") (pinfunction "C_C") (pintype "passive"))
    )
    (net (code "78") (name "unconnected-(D184-PadC)") (class "Default")
      (node (ref "D184") (pin "C") (pinfunction "C_C") (pintype "passive"))
    )
    (net (code "79") (name "unconnected-(D185-PadC)") (class "Default")
      (node (ref "D185") (pin "C") (pinfunction "C_C") (pintype "passive"))
    )
    (net (code "80") (name "unconnected-(D186-PadC)") (class "Default")
      (node (ref "D186") (pin "C") (pinfunction "C_C") (pintype "passive"))
    )
    (net (code "81") (name "unconnected-(D187-PadC)") (class "Default")
      (node (ref "D187") (pin "C") (pinfunction "C_C") (pintype "passive"))
    )
    (net (code "82") (name "unconnected-(D188-PadC)") (class "Default")
      (node (ref "D188") (pin "C") (pinfunction "C_C") (pintype "passive"))
    )
  )
)
